# deflectorshield.net
KiCad netlist of a schematic drawn in EAGLE
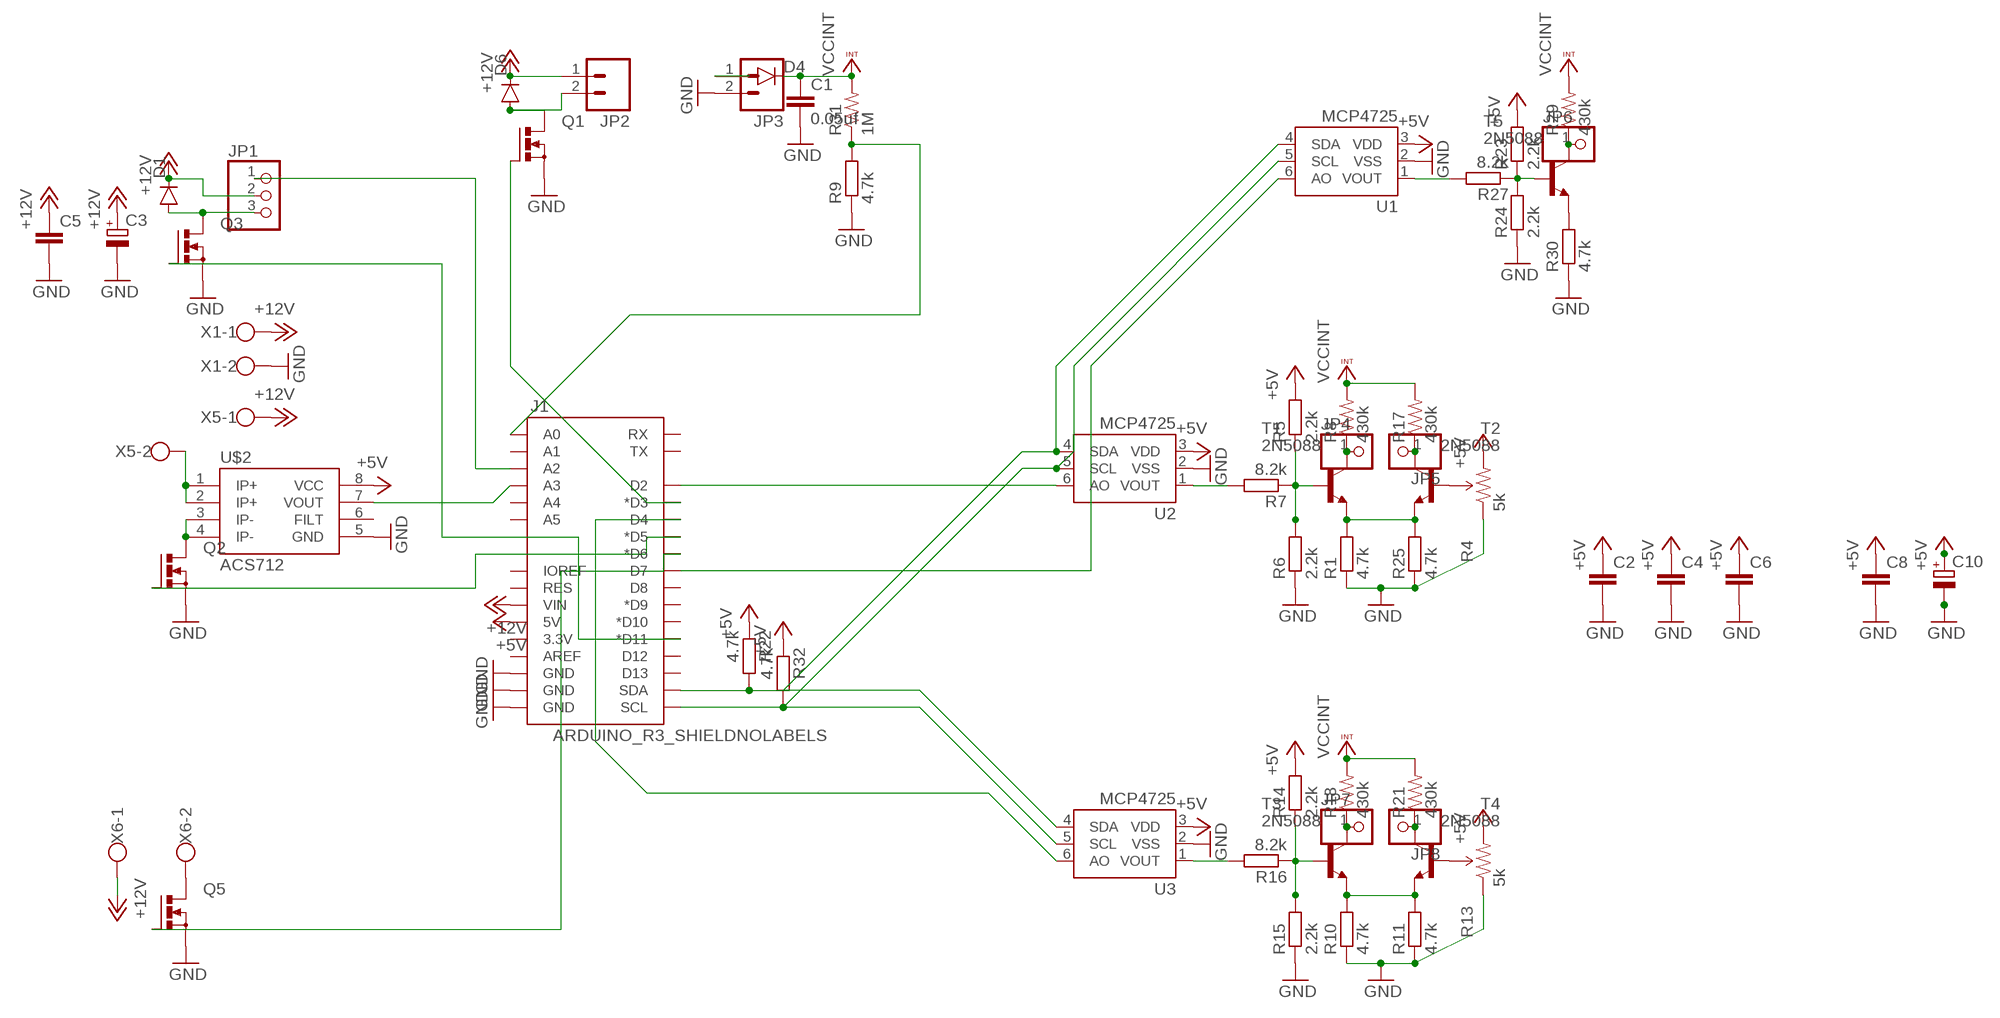
[diagram p0: schematic, sheet 1]

(export (version "E")
  (design (tool "Eeschema 10.0.6"))
  (components
    (comp (ref "C1")
      (value "0.05uf")
      (footprint "eagle-import:C1206")
      (libsource (lib "eagle-import") (part "CC1206"))
    )
    (comp (ref "C2")
      (value "C-EUC0603")
      (footprint "eagle-import:C0603")
      (libsource (lib "eagle-import") (part "C-EUC0603"))
    )
    (comp (ref "C3")
      (value "CPOL-EUE5-13")
      (footprint "eagle-import:E5-13")
      (libsource (lib "eagle-import") (part "CPOL-EUE5-13"))
    )
    (comp (ref "C4")
      (value "C-EUC0603")
      (footprint "eagle-import:C0603")
      (libsource (lib "eagle-import") (part "C-EUC0603"))
    )
    (comp (ref "C5")
      (value "C-EUC0805")
      (footprint "eagle-import:C0805")
      (libsource (lib "eagle-import") (part "resistor_C-EUC0805"))
    )
    (comp (ref "C6")
      (value "C-EUC0603")
      (footprint "eagle-import:C0603")
      (libsource (lib "eagle-import") (part "C-EUC0603"))
    )
    (comp (ref "C8")
      (value "C-EUC0603")
      (footprint "eagle-import:C0603")
      (libsource (lib "eagle-import") (part "C-EUC0603"))
    )
    (comp (ref "C10")
      (value "CPOL-EUE5-6")
      (footprint "eagle-import:E5-6")
      (libsource (lib "eagle-import") (part "CPOL-EUE5-6"))
    )
    (comp (ref "D1")
      (value "DIODESOD123")
      (footprint "eagle-import:SOD-123")
      (libsource (lib "eagle-import") (part "DIODESOD123"))
    )
    (comp (ref "D4")
      (value "DIODESOD123")
      (footprint "eagle-import:SOD-123")
      (libsource (lib "eagle-import") (part "DIODESOD123"))
    )
    (comp (ref "D6")
      (value "DIODESOD123")
      (footprint "eagle-import:SOD-123")
      (libsource (lib "eagle-import") (part "DIODESOD123"))
    )
    (comp (ref "J1")
      (value "ARDUINO_R3_SHIELDNOLABELS")
      (footprint "eagle-import:UNO_R3_SHIELD_NOLABELS")
      (libsource (lib "eagle-import") (part "ARDUINO_R3_SHIELDNOLABELS"))
    )
    (comp (ref "JP1")
      (value "PINHD-1X3")
      (footprint "eagle-import:1X03")
      (libsource (lib "eagle-import") (part "PINHD-1X3"))
    )
    (comp (ref "JP2")
      (value "M02PTH")
      (footprint "eagle-import:1X02")
      (libsource (lib "eagle-import") (part "M02PTH"))
    )
    (comp (ref "JP3")
      (value "M02PTH")
      (footprint "eagle-import:1X02")
      (libsource (lib "eagle-import") (part "M02PTH"))
    )
    (comp (ref "JP4")
      (value "PINHD-1X1")
      (footprint "eagle-import:1X01")
      (libsource (lib "eagle-import") (part "PINHD-1X1"))
    )
    (comp (ref "JP5")
      (value "PINHD-1X1")
      (footprint "eagle-import:1X01")
      (libsource (lib "eagle-import") (part "PINHD-1X1"))
    )
    (comp (ref "JP6")
      (value "PINHD-1X1")
      (footprint "eagle-import:1X01")
      (libsource (lib "eagle-import") (part "PINHD-1X1"))
    )
    (comp (ref "JP7")
      (value "PINHD-1X1")
      (footprint "eagle-import:1X01")
      (libsource (lib "eagle-import") (part "PINHD-1X1"))
    )
    (comp (ref "JP8")
      (value "PINHD-1X1")
      (footprint "eagle-import:1X01")
      (libsource (lib "eagle-import") (part "PINHD-1X1"))
    )
    (comp (ref "Q1")
      (value "N-MOSFET-SO8S")
      (footprint "eagle-import:SO-08")
      (libsource (lib "eagle-import") (part "N-MOSFET-SO8S"))
    )
    (comp (ref "Q2")
      (value "N-MOSFET-SO8S")
      (footprint "eagle-import:SO-08")
      (libsource (lib "eagle-import") (part "N-MOSFET-SO8S"))
    )
    (comp (ref "Q3")
      (value "N-MOSFET-SO8S")
      (footprint "eagle-import:SO-08")
      (libsource (lib "eagle-import") (part "N-MOSFET-SO8S"))
    )
    (comp (ref "Q5")
      (value "N-MOSFET-SO8S")
      (footprint "eagle-import:SO-08")
      (libsource (lib "eagle-import") (part "N-MOSFET-SO8S"))
    )
    (comp (ref "R1")
      (value "4.7k")
      (footprint "eagle-import:R0603")
      (libsource (lib "eagle-import") (part "R-EU_R0603"))
    )
    (comp (ref "R4")
      (value "5k")
      (footprint "eagle-import:TRIMPOT_PTH_S3_LOCK")
      (libsource (lib "eagle-import") (part "TRIMPOTTRIMPOT_PTH_S3_LOCK"))
    )
    (comp (ref "R5")
      (value "2.2k")
      (footprint "eagle-import:R0603")
      (libsource (lib "eagle-import") (part "R-EU_R0603"))
    )
    (comp (ref "R6")
      (value "2.2k")
      (footprint "eagle-import:R0603")
      (libsource (lib "eagle-import") (part "R-EU_R0603"))
    )
    (comp (ref "R7")
      (value "8.2k")
      (footprint "eagle-import:R0603")
      (libsource (lib "eagle-import") (part "R-EU_R0603"))
    )
    (comp (ref "R8")
      (value "430k")
      (footprint "eagle-import:1206")
      (libsource (lib "eagle-import") (part "RESISTOR1206"))
    )
    (comp (ref "R9")
      (value "4.7k")
      (footprint "eagle-import:R0603")
      (libsource (lib "eagle-import") (part "R-EU_R0603"))
    )
    (comp (ref "R10")
      (value "4.7k")
      (footprint "eagle-import:R0603")
      (libsource (lib "eagle-import") (part "R-EU_R0603"))
    )
    (comp (ref "R11")
      (value "4.7k")
      (footprint "eagle-import:R0603")
      (libsource (lib "eagle-import") (part "R-EU_R0603"))
    )
    (comp (ref "R13")
      (value "5k")
      (footprint "eagle-import:TRIMPOT_PTH_S3_LOCK")
      (libsource (lib "eagle-import") (part "TRIMPOTTRIMPOT_PTH_S3_LOCK"))
    )
    (comp (ref "R14")
      (value "2.2k")
      (footprint "eagle-import:R0603")
      (libsource (lib "eagle-import") (part "R-EU_R0603"))
    )
    (comp (ref "R15")
      (value "2.2k")
      (footprint "eagle-import:R0603")
      (libsource (lib "eagle-import") (part "R-EU_R0603"))
    )
    (comp (ref "R16")
      (value "8.2k")
      (footprint "eagle-import:R0603")
      (libsource (lib "eagle-import") (part "R-EU_R0603"))
    )
    (comp (ref "R17")
      (value "430k")
      (footprint "eagle-import:1206")
      (libsource (lib "eagle-import") (part "RESISTOR1206"))
    )
    (comp (ref "R18")
      (value "430k")
      (footprint "eagle-import:1206")
      (libsource (lib "eagle-import") (part "RESISTOR1206"))
    )
    (comp (ref "R21")
      (value "430k")
      (footprint "eagle-import:1206")
      (libsource (lib "eagle-import") (part "RESISTOR1206"))
    )
    (comp (ref "R22")
      (value "4.7k")
      (footprint "eagle-import:R0603")
      (libsource (lib "eagle-import") (part "R-EU_R0603"))
    )
    (comp (ref "R23")
      (value "2.2k")
      (footprint "eagle-import:R0603")
      (libsource (lib "eagle-import") (part "R-EU_R0603"))
    )
    (comp (ref "R24")
      (value "2.2k")
      (footprint "eagle-import:R0603")
      (libsource (lib "eagle-import") (part "R-EU_R0603"))
    )
    (comp (ref "R25")
      (value "4.7k")
      (footprint "eagle-import:R0603")
      (libsource (lib "eagle-import") (part "R-EU_R0603"))
    )
    (comp (ref "R27")
      (value "8.2k")
      (footprint "eagle-import:R0603")
      (libsource (lib "eagle-import") (part "R-EU_R0603"))
    )
    (comp (ref "R29")
      (value "430k")
      (footprint "eagle-import:1206")
      (libsource (lib "eagle-import") (part "RESISTOR1206"))
    )
    (comp (ref "R30")
      (value "4.7k")
      (footprint "eagle-import:R0603")
      (libsource (lib "eagle-import") (part "R-EU_R0603"))
    )
    (comp (ref "R31")
      (value "1M")
      (footprint "eagle-import:1206")
      (libsource (lib "eagle-import") (part "RESISTOR1206"))
    )
    (comp (ref "R32")
      (value "4.7k")
      (footprint "eagle-import:R0603")
      (libsource (lib "eagle-import") (part "R-EU_R0603"))
    )
    (comp (ref "T1")
      (value "2N5088")
      (footprint "eagle-import:TO92")
      (libsource (lib "eagle-import") (part "2N5088"))
    )
    (comp (ref "T2")
      (value "2N5088")
      (footprint "eagle-import:TO92")
      (libsource (lib "eagle-import") (part "2N5088"))
    )
    (comp (ref "T3")
      (value "2N5088")
      (footprint "eagle-import:TO92")
      (libsource (lib "eagle-import") (part "2N5088"))
    )
    (comp (ref "T4")
      (value "2N5088")
      (footprint "eagle-import:TO92")
      (libsource (lib "eagle-import") (part "2N5088"))
    )
    (comp (ref "T5")
      (value "2N5088")
      (footprint "eagle-import:TO92")
      (libsource (lib "eagle-import") (part "2N5088"))
    )
    (comp (ref "U$2")
      (value "ACS712")
      (footprint "eagle-import:SO08")
      (libsource (lib "eagle-import") (part "ACS712"))
    )
    (comp (ref "U1")
      (value "MCP4725")
      (footprint "eagle-import:SOT23-6")
      (libsource (lib "eagle-import") (part "MCP4725SOT-23"))
    )
    (comp (ref "U2")
      (value "MCP4725")
      (footprint "eagle-import:SOT23-6")
      (libsource (lib "eagle-import") (part "MCP4725SOT-23"))
    )
    (comp (ref "U3")
      (value "MCP4725")
      (footprint "eagle-import:SOT23-6")
      (libsource (lib "eagle-import") (part "MCP4725SOT-23"))
    )
    (comp (ref "X1")
      (value "W237-102")
      (footprint "eagle-import:W237-102")
      (fields (field (name "MPN") "237-102"))
      (libsource (lib "eagle-import") (part "W237-102"))
    )
    (comp (ref "X5")
      (value "W237-102")
      (footprint "eagle-import:W237-102")
      (fields (field (name "MPN") "237-102"))
      (libsource (lib "eagle-import") (part "W237-102"))
    )
    (comp (ref "X6")
      (value "W237-102")
      (footprint "eagle-import:W237-102")
      (fields (field (name "MPN") "237-102"))
      (libsource (lib "eagle-import") (part "W237-102"))
    )
  )
  (nets
    (net (code "1") (name "+5V") (class "Default")
      (node (ref "C10") (pin "+") (pinfunction "+_+") (pintype "passive"))
      (node (ref "C2") (pin "1") (pinfunction "1_1") (pintype "passive"))
      (node (ref "C4") (pin "1") (pinfunction "1_1") (pintype "passive"))
      (node (ref "C6") (pin "1") (pinfunction "1_1") (pintype "passive"))
      (node (ref "C8") (pin "1") (pinfunction "1_1") (pintype "passive"))
      (node (ref "J1") (pin "5V") (pinfunction "5V_5V") (pintype "bidirectional"))
      (node (ref "R13") (pin "3") (pinfunction "CW_3") (pintype "passive"))
      (node (ref "R14") (pin "2") (pinfunction "2_2") (pintype "passive"))
      (node (ref "R22") (pin "1") (pinfunction "1_1") (pintype "passive"))
      (node (ref "R23") (pin "2") (pinfunction "2_2") (pintype "passive"))
      (node (ref "R32") (pin "1") (pinfunction "1_1") (pintype "passive"))
      (node (ref "R4") (pin "3") (pinfunction "CW_3") (pintype "passive"))
      (node (ref "R5") (pin "2") (pinfunction "2_2") (pintype "passive"))
      (node (ref "U$2") (pin "8") (pinfunction "VCC_8") (pintype "bidirectional"))
      (node (ref "U1") (pin "3") (pinfunction "VDD_3") (pintype "bidirectional"))
      (node (ref "U2") (pin "3") (pinfunction "VDD_3") (pintype "bidirectional"))
      (node (ref "U3") (pin "3") (pinfunction "VDD_3") (pintype "bidirectional"))
    )
    (net (code "2") (name "+12V") (class "Default")
      (node (ref "C3") (pin "+") (pinfunction "+_+") (pintype "passive"))
      (node (ref "C5") (pin "1") (pinfunction "1_1") (pintype "passive"))
      (node (ref "D1") (pin "C") (pinfunction "C_C") (pintype "passive"))
      (node (ref "D6") (pin "C") (pinfunction "C_C") (pintype "passive"))
      (node (ref "J1") (pin "VIN") (pinfunction "VIN_VIN") (pintype "bidirectional"))
      (node (ref "JP1") (pin "2") (pinfunction "2_2") (pintype "passive"))
      (node (ref "JP2") (pin "1") (pinfunction "1_1") (pintype "passive"))
      (node (ref "X1") (pin "1") (pinfunction "KL_1") (pintype "passive"))
      (node (ref "X5") (pin "1") (pinfunction "KL_1") (pintype "passive"))
      (node (ref "X6") (pin "1") (pinfunction "KL_1") (pintype "passive"))
    )
    (net (code "3") (name "GND") (class "Default")
      (node (ref "C1") (pin "2") (pinfunction "2_2") (pintype "passive"))
      (node (ref "C10") (pin "-") (pinfunction "-_-") (pintype "passive"))
      (node (ref "C2") (pin "2") (pinfunction "2_2") (pintype "passive"))
      (node (ref "C3") (pin "-") (pinfunction "-_-") (pintype "passive"))
      (node (ref "C4") (pin "2") (pinfunction "2_2") (pintype "passive"))
      (node (ref "C5") (pin "2") (pinfunction "2_2") (pintype "passive"))
      (node (ref "C6") (pin "2") (pinfunction "2_2") (pintype "passive"))
      (node (ref "C8") (pin "2") (pinfunction "2_2") (pintype "passive"))
      (node (ref "J1") (pin "GND@0") (pinfunction "GND_GND@0") (pintype "bidirectional"))
      (node (ref "J1") (pin "GND@1") (pinfunction "GND_GND@1") (pintype "bidirectional"))
      (node (ref "J1") (pin "GND@2") (pinfunction "GND_GND@2") (pintype "bidirectional"))
      (node (ref "JP3") (pin "2") (pinfunction "2_2") (pintype "passive"))
      (node (ref "Q1") (pin "1") (pinfunction "S_1") (pintype "passive"))
      (node (ref "Q1") (pin "2") (pinfunction "S_2") (pintype "passive"))
      (node (ref "Q1") (pin "3") (pinfunction "S_3") (pintype "passive"))
      (node (ref "Q2") (pin "1") (pinfunction "S_1") (pintype "passive"))
      (node (ref "Q2") (pin "2") (pinfunction "S_2") (pintype "passive"))
      (node (ref "Q2") (pin "3") (pinfunction "S_3") (pintype "passive"))
      (node (ref "Q3") (pin "1") (pinfunction "S_1") (pintype "passive"))
      (node (ref "Q3") (pin "2") (pinfunction "S_2") (pintype "passive"))
      (node (ref "Q3") (pin "3") (pinfunction "S_3") (pintype "passive"))
      (node (ref "Q5") (pin "1") (pinfunction "S_1") (pintype "passive"))
      (node (ref "Q5") (pin "2") (pinfunction "S_2") (pintype "passive"))
      (node (ref "Q5") (pin "3") (pinfunction "S_3") (pintype "passive"))
      (node (ref "R1") (pin "1") (pinfunction "1_1") (pintype "passive"))
      (node (ref "R10") (pin "1") (pinfunction "1_1") (pintype "passive"))
      (node (ref "R11") (pin "1") (pinfunction "1_1") (pintype "passive"))
      (node (ref "R13") (pin "1") (pinfunction "CCW_1") (pintype "passive"))
      (node (ref "R15") (pin "1") (pinfunction "1_1") (pintype "passive"))
      (node (ref "R24") (pin "1") (pinfunction "1_1") (pintype "passive"))
      (node (ref "R25") (pin "1") (pinfunction "1_1") (pintype "passive"))
      (node (ref "R30") (pin "1") (pinfunction "1_1") (pintype "passive"))
      (node (ref "R4") (pin "1") (pinfunction "CCW_1") (pintype "passive"))
      (node (ref "R6") (pin "1") (pinfunction "1_1") (pintype "passive"))
      (node (ref "R9") (pin "1") (pinfunction "1_1") (pintype "passive"))
      (node (ref "U$2") (pin "5") (pinfunction "GND_5") (pintype "bidirectional"))
      (node (ref "U1") (pin "2") (pinfunction "VSS_2") (pintype "bidirectional"))
      (node (ref "U2") (pin "2") (pinfunction "VSS_2") (pintype "bidirectional"))
      (node (ref "U3") (pin "2") (pinfunction "VSS_2") (pintype "bidirectional"))
      (node (ref "X1") (pin "2") (pinfunction "KL_2") (pintype "passive"))
    )
    (net (code "4") (name "Net-(D1-PadA)") (class "Default")
      (node (ref "D1") (pin "A") (pinfunction "A_A") (pintype "passive"))
      (node (ref "JP1") (pin "3") (pinfunction "3_3") (pintype "passive"))
      (node (ref "Q3") (pin "5") (pinfunction "D_5") (pintype "passive"))
      (node (ref "Q3") (pin "6") (pinfunction "D_6") (pintype "passive"))
      (node (ref "Q3") (pin "7") (pinfunction "D_7") (pintype "passive"))
      (node (ref "Q3") (pin "8") (pinfunction "D_8") (pintype "passive"))
    )
    (net (code "5") (name "Net-(D4-PadA)") (class "Default")
      (node (ref "D4") (pin "A") (pinfunction "A_A") (pintype "passive"))
      (node (ref "JP3") (pin "1") (pinfunction "1_1") (pintype "passive"))
    )
    (net (code "6") (name "Net-(D6-PadA)") (class "Default")
      (node (ref "D6") (pin "A") (pinfunction "A_A") (pintype "passive"))
      (node (ref "JP2") (pin "2") (pinfunction "2_2") (pintype "passive"))
      (node (ref "Q1") (pin "5") (pinfunction "D_5") (pintype "passive"))
      (node (ref "Q1") (pin "6") (pinfunction "D_6") (pintype "passive"))
      (node (ref "Q1") (pin "7") (pinfunction "D_7") (pintype "passive"))
      (node (ref "Q1") (pin "8") (pinfunction "D_8") (pintype "passive"))
    )
    (net (code "7") (name "Net-(J1-*D3)") (class "Default")
      (node (ref "J1") (pin "D3") (pinfunction "*D3_D3") (pintype "bidirectional"))
      (node (ref "Q1") (pin "4") (pinfunction "G_4") (pintype "passive"))
    )
    (net (code "8") (name "Net-(J1-*D5)") (class "Default")
      (node (ref "J1") (pin "D5") (pinfunction "*D5_D5") (pintype "bidirectional"))
      (node (ref "Q2") (pin "4") (pinfunction "G_4") (pintype "passive"))
    )
    (net (code "9") (name "Net-(J1-*D6)") (class "Default")
      (node (ref "J1") (pin "D6") (pinfunction "*D6_D6") (pintype "bidirectional"))
      (node (ref "Q5") (pin "4") (pinfunction "G_4") (pintype "passive"))
    )
    (net (code "10") (name "Net-(J1-*D11)") (class "Default")
      (node (ref "J1") (pin "D11") (pinfunction "*D11_D11") (pintype "bidirectional"))
      (node (ref "Q3") (pin "4") (pinfunction "G_4") (pintype "passive"))
    )
    (net (code "11") (name "Net-(J1-PadA0)") (class "Default")
      (node (ref "J1") (pin "A0") (pinfunction "A0_A0") (pintype "bidirectional"))
      (node (ref "R31") (pin "1") (pinfunction "1_1") (pintype "passive"))
      (node (ref "R9") (pin "2") (pinfunction "2_2") (pintype "passive"))
    )
    (net (code "12") (name "Net-(J1-PadA2)") (class "Default")
      (node (ref "J1") (pin "A2") (pinfunction "A2_A2") (pintype "bidirectional"))
      (node (ref "JP1") (pin "1") (pinfunction "1_1") (pintype "passive"))
    )
    (net (code "13") (name "Net-(Q2-D-Pad5)") (class "Default")
      (node (ref "Q2") (pin "5") (pinfunction "D_5") (pintype "passive"))
      (node (ref "Q2") (pin "6") (pinfunction "D_6") (pintype "passive"))
      (node (ref "Q2") (pin "7") (pinfunction "D_7") (pintype "passive"))
      (node (ref "Q2") (pin "8") (pinfunction "D_8") (pintype "passive"))
      (node (ref "U$2") (pin "3") (pinfunction "IP-_3") (pintype "bidirectional"))
      (node (ref "U$2") (pin "4") (pinfunction "IP-_4") (pintype "bidirectional"))
    )
    (net (code "14") (name "Net-(R4-WIPER)") (class "Default")
      (node (ref "R4") (pin "2") (pinfunction "WIPER_2") (pintype "passive"))
      (node (ref "T2") (pin "2") (pinfunction "B_2") (pintype "passive"))
    )
    (net (code "15") (name "Net-(R13-WIPER)") (class "Default")
      (node (ref "R13") (pin "2") (pinfunction "WIPER_2") (pintype "passive"))
      (node (ref "T4") (pin "2") (pinfunction "B_2") (pintype "passive"))
    )
    (net (code "16") (name "Net-(T1-B)") (class "Default")
      (node (ref "R5") (pin "1") (pinfunction "1_1") (pintype "passive"))
      (node (ref "R6") (pin "2") (pinfunction "2_2") (pintype "passive"))
      (node (ref "R7") (pin "1") (pinfunction "1_1") (pintype "passive"))
      (node (ref "T1") (pin "2") (pinfunction "B_2") (pintype "passive"))
    )
    (net (code "17") (name "Net-(T1-C)") (class "Default")
      (node (ref "JP4") (pin "1") (pinfunction "1_1") (pintype "passive"))
      (node (ref "R8") (pin "1") (pinfunction "1_1") (pintype "passive"))
      (node (ref "T1") (pin "1") (pinfunction "C_1") (pintype "passive"))
    )
    (net (code "18") (name "Net-(T1-E)") (class "Default")
      (node (ref "R1") (pin "2") (pinfunction "2_2") (pintype "passive"))
      (node (ref "R25") (pin "2") (pinfunction "2_2") (pintype "passive"))
      (node (ref "T1") (pin "3") (pinfunction "E_3") (pintype "passive"))
      (node (ref "T2") (pin "3") (pinfunction "E_3") (pintype "passive"))
    )
    (net (code "19") (name "Net-(T2-C)") (class "Default")
      (node (ref "JP5") (pin "1") (pinfunction "1_1") (pintype "passive"))
      (node (ref "R17") (pin "1") (pinfunction "1_1") (pintype "passive"))
      (node (ref "T2") (pin "1") (pinfunction "C_1") (pintype "passive"))
    )
    (net (code "20") (name "Net-(T3-B)") (class "Default")
      (node (ref "R14") (pin "1") (pinfunction "1_1") (pintype "passive"))
      (node (ref "R15") (pin "2") (pinfunction "2_2") (pintype "passive"))
      (node (ref "R16") (pin "1") (pinfunction "1_1") (pintype "passive"))
      (node (ref "T3") (pin "2") (pinfunction "B_2") (pintype "passive"))
    )
    (net (code "21") (name "Net-(T3-C)") (class "Default")
      (node (ref "JP7") (pin "1") (pinfunction "1_1") (pintype "passive"))
      (node (ref "R18") (pin "1") (pinfunction "1_1") (pintype "passive"))
      (node (ref "T3") (pin "1") (pinfunction "C_1") (pintype "passive"))
    )
    (net (code "22") (name "Net-(T3-E)") (class "Default")
      (node (ref "R10") (pin "2") (pinfunction "2_2") (pintype "passive"))
      (node (ref "R11") (pin "2") (pinfunction "2_2") (pintype "passive"))
      (node (ref "T3") (pin "3") (pinfunction "E_3") (pintype "passive"))
      (node (ref "T4") (pin "3") (pinfunction "E_3") (pintype "passive"))
    )
    (net (code "23") (name "Net-(T4-C)") (class "Default")
      (node (ref "JP8") (pin "1") (pinfunction "1_1") (pintype "passive"))
      (node (ref "R21") (pin "1") (pinfunction "1_1") (pintype "passive"))
      (node (ref "T4") (pin "1") (pinfunction "C_1") (pintype "passive"))
    )
    (net (code "24") (name "Net-(T5-B)") (class "Default")
      (node (ref "R23") (pin "1") (pinfunction "1_1") (pintype "passive"))
      (node (ref "R24") (pin "2") (pinfunction "2_2") (pintype "passive"))
      (node (ref "R27") (pin "1") (pinfunction "1_1") (pintype "passive"))
      (node (ref "T5") (pin "2") (pinfunction "B_2") (pintype "passive"))
    )
    (net (code "25") (name "Net-(T5-C)") (class "Default")
      (node (ref "JP6") (pin "1") (pinfunction "1_1") (pintype "passive"))
      (node (ref "R29") (pin "1") (pinfunction "1_1") (pintype "passive"))
      (node (ref "T5") (pin "1") (pinfunction "C_1") (pintype "passive"))
    )
    (net (code "26") (name "Net-(T5-E)") (class "Default")
      (node (ref "R30") (pin "2") (pinfunction "2_2") (pintype "passive"))
      (node (ref "T5") (pin "3") (pinfunction "E_3") (pintype "passive"))
    )
    (net (code "27") (name "Net-(U$2-VOUT)") (class "Default")
      (node (ref "J1") (pin "A3") (pinfunction "A3_A3") (pintype "bidirectional"))
      (node (ref "U$2") (pin "7") (pinfunction "VOUT_7") (pintype "bidirectional"))
    )
    (net (code "28") (name "Net-(U1-AO)") (class "Default")
      (node (ref "J1") (pin "D7") (pinfunction "D7_D7") (pintype "bidirectional"))
      (node (ref "U1") (pin "6") (pinfunction "AO_6") (pintype "bidirectional"))
    )
    (net (code "29") (name "Net-(U1-SCL)") (class "Default")
      (node (ref "J1") (pin "SCL") (pinfunction "SCL_SCL") (pintype "bidirectional"))
      (node (ref "R32") (pin "2") (pinfunction "2_2") (pintype "passive"))
      (node (ref "U1") (pin "5") (pinfunction "SCL_5") (pintype "bidirectional"))
      (node (ref "U2") (pin "5") (pinfunction "SCL_5") (pintype "bidirectional"))
      (node (ref "U3") (pin "5") (pinfunction "SCL_5") (pintype "bidirectional"))
    )
    (net (code "30") (name "Net-(U1-SDA)") (class "Default")
      (node (ref "J1") (pin "SDA") (pinfunction "SDA_SDA") (pintype "bidirectional"))
      (node (ref "R22") (pin "2") (pinfunction "2_2") (pintype "passive"))
      (node (ref "U1") (pin "4") (pinfunction "SDA_4") (pintype "bidirectional"))
      (node (ref "U2") (pin "4") (pinfunction "SDA_4") (pintype "bidirectional"))
      (node (ref "U3") (pin "4") (pinfunction "SDA_4") (pintype "bidirectional"))
    )
    (net (code "31") (name "Net-(U1-VOUT)") (class "Default")
      (node (ref "R27") (pin "2") (pinfunction "2_2") (pintype "passive"))
      (node (ref "U1") (pin "1") (pinfunction "VOUT_1") (pintype "bidirectional"))
    )
    (net (code "32") (name "Net-(U2-AO)") (class "Default")
      (node (ref "J1") (pin "D2") (pinfunction "D2_D2") (pintype "bidirectional"))
      (node (ref "U2") (pin "6") (pinfunction "AO_6") (pintype "bidirectional"))
    )
    (net (code "33") (name "Net-(U2-VOUT)") (class "Default")
      (node (ref "R7") (pin "2") (pinfunction "2_2") (pintype "passive"))
      (node (ref "U2") (pin "1") (pinfunction "VOUT_1") (pintype "bidirectional"))
    )
    (net (code "34") (name "Net-(U3-AO)") (class "Default")
      (node (ref "J1") (pin "D4") (pinfunction "D4_D4") (pintype "bidirectional"))
      (node (ref "U3") (pin "6") (pinfunction "AO_6") (pintype "bidirectional"))
    )
    (net (code "35") (name "Net-(U3-VOUT)") (class "Default")
      (node (ref "R16") (pin "2") (pinfunction "2_2") (pintype "passive"))
      (node (ref "U3") (pin "1") (pinfunction "VOUT_1") (pintype "bidirectional"))
    )
    (net (code "36") (name "Net-(X5B-KL)") (class "Default")
      (node (ref "U$2") (pin "1") (pinfunction "IP+_1") (pintype "bidirectional"))
      (node (ref "U$2") (pin "2") (pinfunction "IP+_2") (pintype "bidirectional"))
      (node (ref "X5") (pin "2") (pinfunction "KL_2") (pintype "passive"))
    )
    (net (code "37") (name "Net-(X6B-KL)") (class "Default")
      (node (ref "Q5") (pin "5") (pinfunction "D_5") (pintype "passive"))
      (node (ref "Q5") (pin "6") (pinfunction "D_6") (pintype "passive"))
      (node (ref "Q5") (pin "7") (pinfunction "D_7") (pintype "passive"))
      (node (ref "Q5") (pin "8") (pinfunction "D_8") (pintype "passive"))
      (node (ref "X6") (pin "2") (pinfunction "KL_2") (pintype "passive"))
    )
    (net (code "38") (name "VCCINT") (class "Default")
      (node (ref "C1") (pin "1") (pinfunction "1_1") (pintype "passive"))
      (node (ref "D4") (pin "C") (pinfunction "C_C") (pintype "passive"))
      (node (ref "R17") (pin "2") (pinfunction "2_2") (pintype "passive"))
      (node (ref "R18") (pin "2") (pinfunction "2_2") (pintype "passive"))
      (node (ref "R21") (pin "2") (pinfunction "2_2") (pintype "passive"))
      (node (ref "R29") (pin "2") (pinfunction "2_2") (pintype "passive"))
      (node (ref "R31") (pin "2") (pinfunction "2_2") (pintype "passive"))
      (node (ref "R8") (pin "2") (pinfunction "2_2") (pintype "passive"))
    )
    (net (code "39") (name "unconnected-(J1-*D9-PadD9)") (class "Default")
      (node (ref "J1") (pin "D9") (pinfunction "*D9_D9") (pintype "bidirectional"))
    )
    (net (code "40") (name "unconnected-(J1-*D10-PadD10)") (class "Default")
      (node (ref "J1") (pin "D10") (pinfunction "*D10_D10") (pintype "bidirectional"))
    )
    (net (code "41") (name "unconnected-(J1-Pad3.3V)") (class "Default")
      (node (ref "J1") (pin "3.3V") (pinfunction "3.3V_3.3V") (pintype "bidirectional"))
    )
    (net (code "42") (name "unconnected-(J1-PadA1)") (class "Default")
      (node (ref "J1") (pin "A1") (pinfunction "A1_A1") (pintype "bidirectional"))
    )
    (net (code "43") (name "unconnected-(J1-PadA4)") (class "Default")
      (node (ref "J1") (pin "A4") (pinfunction "A4_A4") (pintype "bidirectional"))
    )
    (net (code "44") (name "unconnected-(J1-PadA5)") (class "Default")
      (node (ref "J1") (pin "A5") (pinfunction "A5_A5") (pintype "bidirectional"))
    )
    (net (code "45") (name "unconnected-(J1-PadAREF)") (class "Default")
      (node (ref "J1") (pin "AREF") (pinfunction "AREF_AREF") (pintype "bidirectional"))
    )
    (net (code "46") (name "unconnected-(J1-PadD8)") (class "Default")
      (node (ref "J1") (pin "D8") (pinfunction "D8_D8") (pintype "bidirectional"))
    )
    (net (code "47") (name "unconnected-(J1-PadD12)") (class "Default")
      (node (ref "J1") (pin "D12") (pinfunction "D12_D12") (pintype "bidirectional"))
    )
    (net (code "48") (name "unconnected-(J1-PadD13)") (class "Default")
      (node (ref "J1") (pin "D13") (pinfunction "D13_D13") (pintype "bidirectional"))
    )
    (net (code "49") (name "unconnected-(J1-PadIOREF)") (class "Default")
      (node (ref "J1") (pin "IOREF") (pinfunction "IOREF_IOREF") (pintype "bidirectional"))
    )
    (net (code "50") (name "unconnected-(J1-PadRES)") (class "Default")
      (node (ref "J1") (pin "RES") (pinfunction "RES_RES") (pintype "bidirectional"))
    )
    (net (code "51") (name "unconnected-(J1-PadRX)") (class "Default")
      (node (ref "J1") (pin "RX") (pinfunction "RX_RX") (pintype "bidirectional"))
    )
    (net (code "52") (name "unconnected-(J1-PadTX)") (class "Default")
      (node (ref "J1") (pin "TX") (pinfunction "TX_TX") (pintype "bidirectional"))
    )
    (net (code "53") (name "unconnected-(U$2-FILT-Pad6)") (class "Default")
      (node (ref "U$2") (pin "6") (pinfunction "FILT_6") (pintype "bidirectional"))
    )
  )
)
